# 01-MCU.net
KiCad netlist of a schematic drawn in Altium Designer
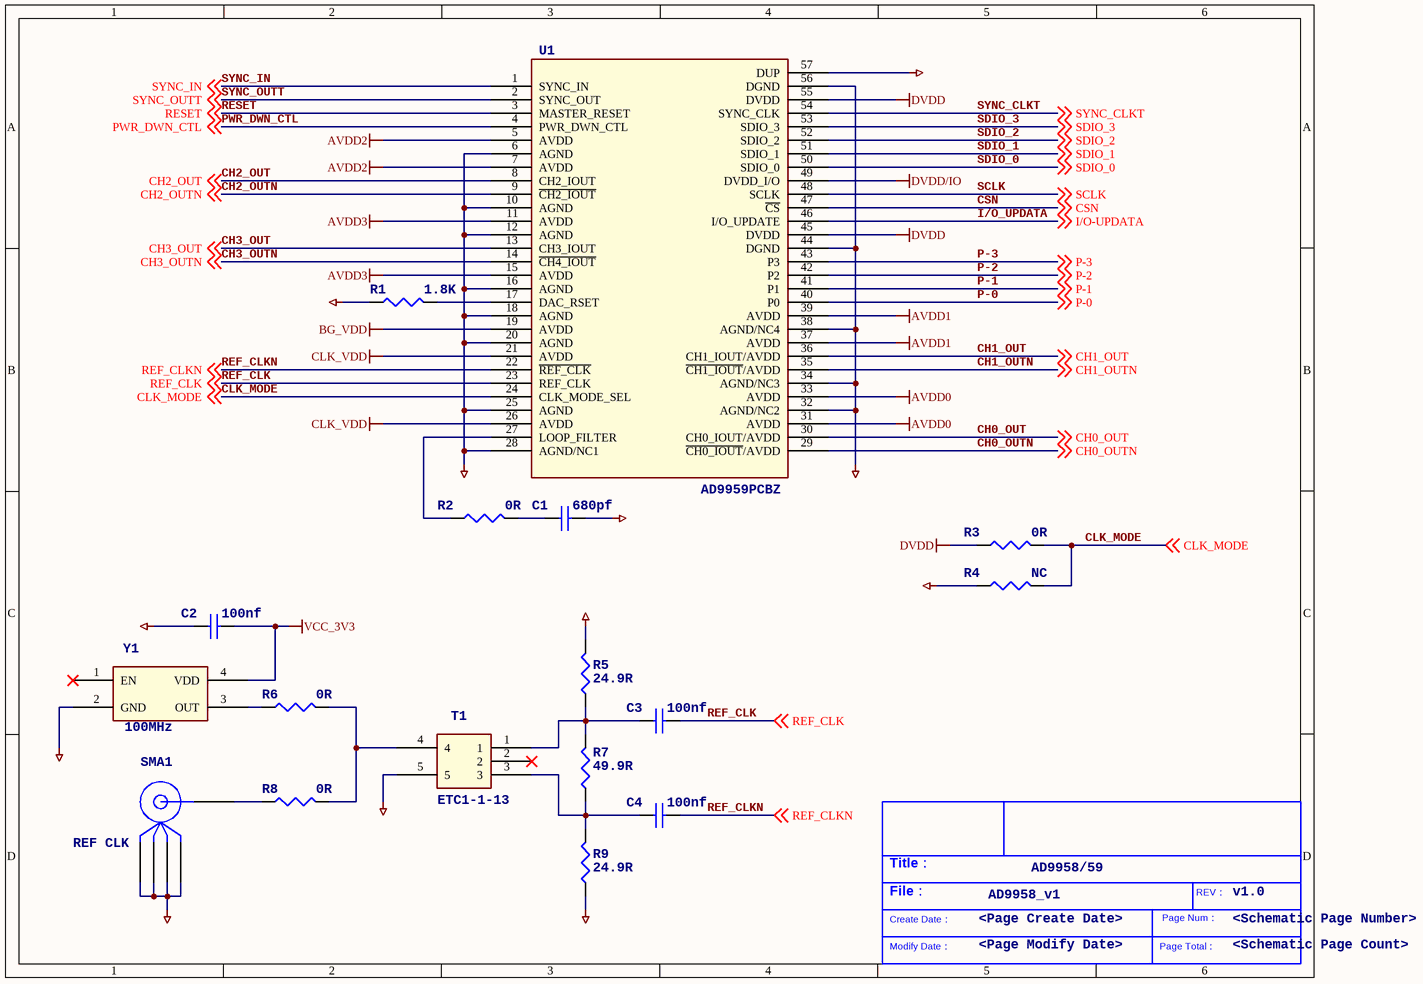
[diagram p0: 01-MCU.SchDoc]

(export (version "E")
  (design (tool "Eeschema 10.0.6"))
  (components
    (comp (ref "C1") (value "680pf") (footprint "0603C") (libsource (lib "*") (part "CAP NP")))
    (comp (ref "C2") (value "100nf") (footprint "0603C") (libsource (lib "*") (part "CAP NP")))
    (comp (ref "C3") (value "100nf") (footprint "0603C") (libsource (lib "*") (part "CAP NP")))
    (comp (ref "C4") (value "100nf") (footprint "0603C") (libsource (lib "*") (part "CAP NP")))
    (comp (ref "R1") (value "1.8K") (footprint "0603R") (libsource (lib "*") (part "R")))
    (comp (ref "R2") (value "0R") (footprint "0603R") (libsource (lib "*") (part "R")))
    (comp (ref "R3") (value "0R") (footprint "0603R") (libsource (lib "*") (part "R")))
    (comp (ref "R4") (value "NC") (footprint "0603R") (libsource (lib "*") (part "R")))
    (comp (ref "R5") (value "24.9R") (footprint "0603R") (libsource (lib "*") (part "R")))
    (comp (ref "R6") (value "0R") (footprint "0603R") (libsource (lib "*") (part "R")))
    (comp (ref "R7") (value "49.9R") (footprint "0603R") (libsource (lib "*") (part "R")))
    (comp (ref "R8") (value "0R") (footprint "0603R") (libsource (lib "*") (part "R")))
    (comp (ref "R9") (value "24.9R") (footprint "0603R") (libsource (lib "*") (part "R")))
    (comp (ref "SMA1") (value "REF CLK") (footprint "CON10-5R1X5R1") (libsource (lib "*") (part "BNC")))
    (comp (ref "T1") (value "ETC1-1-13") (footprint "SM-22") (libsource (lib "*") (part "ETC1-1-13")))
    (comp (ref "U1")
      (value "AD9959PCBZ")
      (footprint "QFN50P800X800X100-56M")
      (libsource (lib "*") (part "AD9958BCPZ_2"))
    )
    (comp (ref "Y1") (value "100MHz") (footprint "XTAL-SMD-7050_4P") (libsource (lib "*") (part "XTAL_SMD")))
  )
  (nets
    (net (code "1") (name "AGND") (class "Default")
      (node (ref "C1") (pin "2") (pinfunction "2_2") (pintype "passive"))
      (node (ref "C2") (pin "1") (pinfunction "1_1") (pintype "passive"))
      (node (ref "R1") (pin "1") (pinfunction "1_1") (pintype "passive"))
      (node (ref "R4") (pin "1") (pinfunction "1_1") (pintype "passive"))
      (node (ref "R5") (pin "2") (pinfunction "2_2") (pintype "passive"))
      (node (ref "R9") (pin "1") (pinfunction "1_1") (pintype "passive"))
      (node (ref "SMA1") (pin "2") (pinfunction "GND_2") (pintype "power_in"))
      (node (ref "SMA1") (pin "3") (pinfunction "GND_3") (pintype "power_in"))
      (node (ref "SMA1") (pin "4") (pinfunction "GND_4") (pintype "power_in"))
      (node (ref "SMA1") (pin "5") (pinfunction "GND_5") (pintype "power_in"))
      (node (ref "T1") (pin "5") (pinfunction "5_5") (pintype "passive"))
      (node (ref "U1") (pin "10") (pinfunction "AGND_10") (pintype "power_in"))
      (node (ref "U1") (pin "12") (pinfunction "AGND_12") (pintype "power_in"))
      (node (ref "U1") (pin "16") (pinfunction "AGND_16") (pintype "power_in"))
      (node (ref "U1") (pin "18") (pinfunction "AGND_18") (pintype "power_in"))
      (node (ref "U1") (pin "20") (pinfunction "AGND_20") (pintype "power_in"))
      (node (ref "U1") (pin "25") (pinfunction "AGND_25") (pintype "power_in"))
      (node (ref "U1") (pin "28") (pinfunction "AGND/NC1_28") (pintype "power_in"))
      (node (ref "U1") (pin "32") (pinfunction "AGND/NC2_32") (pintype "power_in"))
      (node (ref "U1") (pin "34") (pinfunction "AGND/NC3_34") (pintype "passive"))
      (node (ref "U1") (pin "38") (pinfunction "AGND/NC4_38") (pintype "passive"))
      (node (ref "U1") (pin "44") (pinfunction "DGND_44") (pintype "power_in"))
      (node (ref "U1") (pin "56") (pinfunction "DGND_56") (pintype "power_in"))
      (node (ref "U1") (pin "57") (pinfunction "DUP_57") (pintype "power_in"))
      (node (ref "U1") (pin "6") (pinfunction "AGND_6") (pintype "power_in"))
      (node (ref "Y1") (pin "2") (pinfunction "GND_2") (pintype "power_in"))
    )
    (net (code "2") (name "AVDD0") (class "Default")
      (node (ref "U1") (pin "31") (pinfunction "AVDD_31") (pintype "power_in"))
      (node (ref "U1") (pin "33") (pinfunction "AVDD_33") (pintype "power_in"))
    )
    (net (code "3") (name "AVDD1") (class "Default")
      (node (ref "U1") (pin "37") (pinfunction "AVDD_37") (pintype "power_in"))
      (node (ref "U1") (pin "39") (pinfunction "AVDD_39") (pintype "power_in"))
    )
    (net (code "4") (name "AVDD2") (class "Default")
      (node (ref "U1") (pin "5") (pinfunction "AVDD_5") (pintype "power_in"))
      (node (ref "U1") (pin "7") (pinfunction "AVDD_7") (pintype "power_in"))
    )
    (net (code "5") (name "AVDD3") (class "Default")
      (node (ref "U1") (pin "11") (pinfunction "AVDD_11") (pintype "power_in"))
      (node (ref "U1") (pin "15") (pinfunction "AVDD_15") (pintype "power_in"))
    )
    (net (code "6") (name "BG_VDD") (class "Default")
      (node (ref "U1") (pin "19") (pinfunction "AVDD_19") (pintype "power_in"))
    )
    (net (code "7") (name "CH0_OUT") (class "Default")
      (node (ref "U1") (pin "30") (pinfunction "CH0_IOUT/AVDD_30") (pintype "power_in"))
    )
    (net (code "8") (name "CH0_OUTN") (class "Default")
      (node (ref "U1") (pin "29") (pinfunction "~{CH0_IOUT}/AVDD_29") (pintype "power_in"))
    )
    (net (code "9") (name "CH1_OUT") (class "Default")
      (node (ref "U1") (pin "36") (pinfunction "CH1_IOUT/AVDD_36") (pintype "power_in"))
    )
    (net (code "10") (name "CH1_OUTN") (class "Default")
      (node (ref "U1") (pin "35") (pinfunction "~{CH1_IOUT}/AVDD_35") (pintype "power_in"))
    )
    (net (code "11") (name "CH2_OUT") (class "Default")
      (node (ref "U1") (pin "8") (pinfunction "CH2_IOUT_8") (pintype "passive"))
    )
    (net (code "12") (name "CH2_OUTN") (class "Default")
      (node (ref "U1") (pin "9") (pinfunction "~{CH2_IOUT}_9") (pintype "passive"))
    )
    (net (code "13") (name "CH3_OUT") (class "Default")
      (node (ref "U1") (pin "13") (pinfunction "CH3_IOUT_13") (pintype "passive"))
    )
    (net (code "14") (name "CH3_OUTN") (class "Default")
      (node (ref "U1") (pin "14") (pinfunction "~{CH4_IOUT}_14") (pintype "passive"))
    )
    (net (code "15") (name "CLK_MODE") (class "Default")
      (node (ref "R3") (pin "2") (pinfunction "2_2") (pintype "passive"))
      (node (ref "R4") (pin "2") (pinfunction "2_2") (pintype "passive"))
      (node (ref "U1") (pin "24") (pinfunction "CLK_MODE_SEL_24") (pintype "passive"))
    )
    (net (code "16") (name "CLK_VDD") (class "Default")
      (node (ref "U1") (pin "21") (pinfunction "AVDD_21") (pintype "power_in"))
      (node (ref "U1") (pin "26") (pinfunction "AVDD_26") (pintype "power_in"))
    )
    (net (code "17") (name "CSN") (class "Default")
      (node (ref "U1") (pin "47") (pinfunction "~{CS}_47") (pintype "passive"))
    )
    (net (code "18") (name "DVDD") (class "Default")
      (node (ref "R3") (pin "1") (pinfunction "1_1") (pintype "passive"))
      (node (ref "U1") (pin "45") (pinfunction "DVDD_45") (pintype "power_in"))
      (node (ref "U1") (pin "55") (pinfunction "DVDD_55") (pintype "power_in"))
    )
    (net (code "19") (name "DVDD{slash}IO") (class "Default")
      (node (ref "U1") (pin "49") (pinfunction "DVDD_I/O_49") (pintype "power_in"))
    )
    (net (code "20") (name "I{slash}O-UPDATA") (class "Default")
      (node (ref "U1") (pin "46") (pinfunction "I/O_UPDATE_46") (pintype "passive"))
    )
    (net (code "21") (name "Net-(C1-Pad1)") (class "Default")
      (node (ref "C1") (pin "1") (pinfunction "1_1") (pintype "passive"))
      (node (ref "R2") (pin "2") (pinfunction "2_2") (pintype "passive"))
    )
    (net (code "22") (name "Net-(C3-Pad1)") (class "Default")
      (node (ref "C3") (pin "1") (pinfunction "1_1") (pintype "passive"))
      (node (ref "R5") (pin "1") (pinfunction "1_1") (pintype "passive"))
      (node (ref "R7") (pin "2") (pinfunction "2_2") (pintype "passive"))
      (node (ref "T1") (pin "1") (pinfunction "1_1") (pintype "passive"))
    )
    (net (code "23") (name "Net-(C4-Pad1)") (class "Default")
      (node (ref "C4") (pin "1") (pinfunction "1_1") (pintype "passive"))
      (node (ref "R7") (pin "1") (pinfunction "1_1") (pintype "passive"))
      (node (ref "R9") (pin "2") (pinfunction "2_2") (pintype "passive"))
      (node (ref "T1") (pin "3") (pinfunction "3_3") (pintype "passive"))
    )
    (net (code "24") (name "Net-(R6-Pad2)") (class "Default")
      (node (ref "R6") (pin "2") (pinfunction "2_2") (pintype "passive"))
      (node (ref "R8") (pin "2") (pinfunction "2_2") (pintype "passive"))
      (node (ref "T1") (pin "4") (pinfunction "4_4") (pintype "passive"))
    )
    (net (code "25") (name "Net-(R8-Pad1)") (class "Default")
      (node (ref "R8") (pin "1") (pinfunction "1_1") (pintype "passive"))
      (node (ref "SMA1") (pin "1") (pinfunction "1_1") (pintype "passive"))
    )
    (net (code "26") (name "Net-(U1-DAC_RSET)") (class "Default")
      (node (ref "R1") (pin "2") (pinfunction "2_2") (pintype "passive"))
      (node (ref "U1") (pin "17") (pinfunction "DAC_RSET_17") (pintype "passive"))
    )
    (net (code "27") (name "Net-(U1-LOOP_FILTER)") (class "Default")
      (node (ref "R2") (pin "1") (pinfunction "1_1") (pintype "passive"))
      (node (ref "U1") (pin "27") (pinfunction "LOOP_FILTER_27") (pintype "passive"))
    )
    (net (code "28") (name "Net-(Y1-OUT)") (class "Default")
      (node (ref "R6") (pin "1") (pinfunction "1_1") (pintype "passive"))
      (node (ref "Y1") (pin "3") (pinfunction "OUT_3") (pintype "passive"))
    )
    (net (code "29") (name "P-0") (class "Default")
      (node (ref "U1") (pin "40") (pinfunction "P0_40") (pintype "passive"))
    )
    (net (code "30") (name "P-1") (class "Default")
      (node (ref "U1") (pin "41") (pinfunction "P1_41") (pintype "passive"))
    )
    (net (code "31") (name "P-2") (class "Default")
      (node (ref "U1") (pin "42") (pinfunction "P2_42") (pintype "passive"))
    )
    (net (code "32") (name "P-3") (class "Default")
      (node (ref "U1") (pin "43") (pinfunction "P3_43") (pintype "passive"))
    )
    (net (code "33") (name "PWR_DWN_CTL") (class "Default")
      (node (ref "U1") (pin "4") (pinfunction "PWR_DWN_CTL_4") (pintype "passive"))
    )
    (net (code "34") (name "REF_CLK") (class "Default")
      (node (ref "C3") (pin "2") (pinfunction "2_2") (pintype "passive"))
      (node (ref "U1") (pin "23") (pinfunction "REF_CLK_23") (pintype "passive"))
    )
    (net (code "35") (name "REF_CLKN") (class "Default")
      (node (ref "C4") (pin "2") (pinfunction "2_2") (pintype "passive"))
      (node (ref "U1") (pin "22") (pinfunction "~{REF_CLK}_22") (pintype "passive"))
    )
    (net (code "36") (name "RESET") (class "Default")
      (node (ref "U1") (pin "3") (pinfunction "MASTER_RESET_3") (pintype "passive"))
    )
    (net (code "37") (name "SCLK") (class "Default")
      (node (ref "U1") (pin "48") (pinfunction "SCLK_48") (pintype "passive"))
    )
    (net (code "38") (name "SDIO_0") (class "Default")
      (node (ref "U1") (pin "50") (pinfunction "SDIO_0_50") (pintype "passive"))
    )
    (net (code "39") (name "SDIO_1") (class "Default")
      (node (ref "U1") (pin "51") (pinfunction "SDIO_1_51") (pintype "passive"))
    )
    (net (code "40") (name "SDIO_2") (class "Default")
      (node (ref "U1") (pin "52") (pinfunction "SDIO_2_52") (pintype "passive"))
    )
    (net (code "41") (name "SDIO_3") (class "Default")
      (node (ref "U1") (pin "53") (pinfunction "SDIO_3_53") (pintype "passive"))
    )
    (net (code "42") (name "SYNC_CLKT") (class "Default")
      (node (ref "U1") (pin "54") (pinfunction "SYNC_CLK_54") (pintype "passive"))
    )
    (net (code "43") (name "SYNC_IN") (class "Default")
      (node (ref "U1") (pin "1") (pinfunction "SYNC_IN_1") (pintype "passive"))
    )
    (net (code "44") (name "SYNC_OUTT") (class "Default")
      (node (ref "U1") (pin "2") (pinfunction "SYNC_OUT_2") (pintype "passive"))
    )
    (net (code "45") (name "VCC_3V3") (class "Default")
      (node (ref "C2") (pin "2") (pinfunction "2_2") (pintype "passive"))
      (node (ref "Y1") (pin "4") (pinfunction "VDD_4") (pintype "power_in"))
    )
    (net (code "46") (name "unconnected-(T1-Pad2)") (class "Default")
      (node (ref "T1") (pin "2") (pinfunction "2_2") (pintype "passive+no_connect"))
    )
    (net (code "47") (name "unconnected-(Y1-EN-Pad1)") (class "Default")
      (node (ref "Y1") (pin "1") (pinfunction "EN_1") (pintype "passive+no_connect"))
    )
  )
)
